# 780-00012-P1_Sch_M2_Focus_Drive_old2.net
KiCad netlist of a schematic drawn in Altium Designer
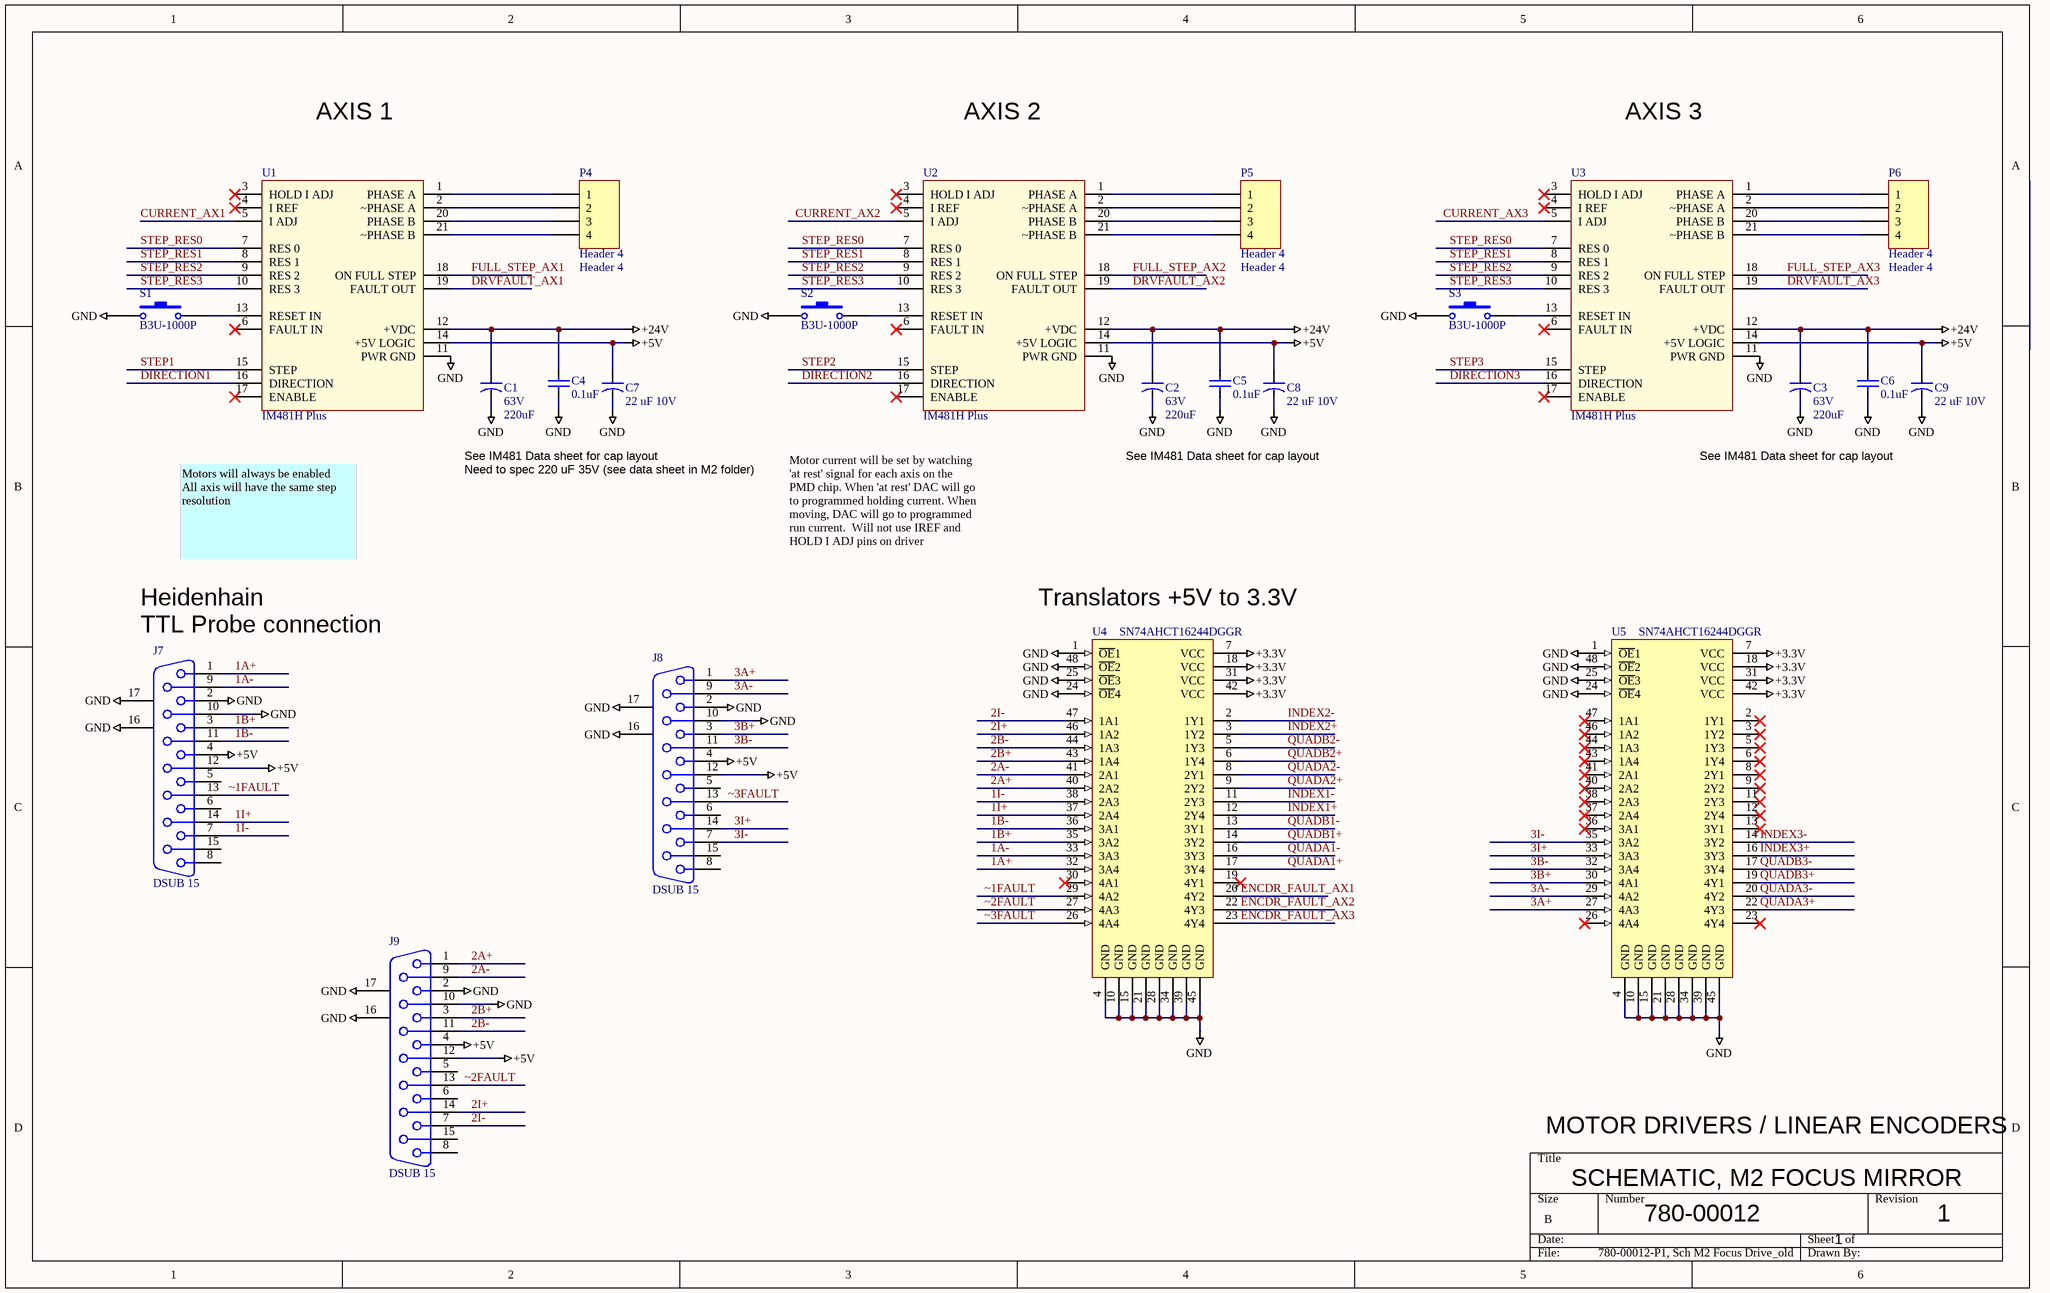
[diagram p0: 780-00012-P1, Sch M2 Focus Drive_old2.SchDoc]

(export (version "E")
  (design (tool "Eeschema 10.0.6"))
  (components
    (comp (ref "C1")
      (value "63V")
      (footprint "CAP 220uF 63V")
      (description "CAP 220UF 63V ELECT MVH SMD")
      (fields (field (name "MANUFACTURER") "United Chemi-Con") (field (name "ALTIUM_VALUE") "220uF"))
      (libsource (lib "Richs Schematic Components") (part "Cap 220uF, 63V"))
    )
    (comp (ref "C2")
      (value "63V")
      (footprint "CAP 220uF 63V")
      (description "CAP 220UF 63V ELECT MVH SMD")
      (fields (field (name "MANUFACTURER") "United Chemi-Con") (field (name "ALTIUM_VALUE") "220uF"))
      (libsource (lib "Richs Schematic Components") (part "Cap 220uF, 63V"))
    )
    (comp (ref "C3")
      (value "63V")
      (footprint "CAP 220uF 63V")
      (description "CAP 220UF 63V ELECT MVH SMD")
      (fields (field (name "MANUFACTURER") "United Chemi-Con") (field (name "ALTIUM_VALUE") "220uF"))
      (libsource (lib "Richs Schematic Components") (part "Cap 220uF, 63V"))
    )
    (comp (ref "C4")
      (value "0.1uF")
      (footprint "SMD_0805")
      (description "Capacitor")
      (fields (field (name "Comment") "Cap SMD"))
      (libsource (lib "Richs Schematic Components") (part "Cap SMD"))
    )
    (comp (ref "C5")
      (value "0.1uF")
      (footprint "SMD_0805")
      (description "Capacitor")
      (fields (field (name "Comment") "Cap SMD"))
      (libsource (lib "Richs Schematic Components") (part "Cap SMD"))
    )
    (comp (ref "C6")
      (value "0.1uF")
      (footprint "SMD_0805")
      (description "Capacitor")
      (fields (field (name "Comment") "Cap SMD"))
      (libsource (lib "Richs Schematic Components") (part "Cap SMD"))
    )
    (comp (ref "C7")
      (value "22 uF 10V")
      (footprint "SMD_CAP_3216")
      (description "outline 3.2mm x 1.6mm")
      (fields (field (name "MANUFACTURER") "KEMET") (field (name "Comment") "16V"))
      (libsource (lib "Richs Schematic Components") (part "Cap Tant 16V"))
    )
    (comp (ref "C8")
      (value "22 uF 10V")
      (footprint "SMD_CAP_3216")
      (description "outline 3.2mm x 1.6mm")
      (fields (field (name "MANUFACTURER") "KEMET") (field (name "Comment") "16V"))
      (libsource (lib "Richs Schematic Components") (part "Cap Tant 16V"))
    )
    (comp (ref "C9")
      (value "22 uF 10V")
      (footprint "SMD_CAP_3216")
      (description "outline 3.2mm x 1.6mm")
      (fields (field (name "MANUFACTURER") "KEMET") (field (name "Comment") "16V"))
      (libsource (lib "Richs Schematic Components") (part "Cap Tant 16V"))
    )
    (comp (ref "J7")
      (value "DSUB 15")
      (footprint "DSUB15 PCB VERT Female")
      (description "Receptacle Assembly, 15 Position")
      (fields (field (name "PUBLISHER") "Altium Limited"))
      (libsource (lib "Richs Schematic Components") (part "DSUB 15"))
    )
    (comp (ref "J8")
      (value "DSUB 15")
      (footprint "DSUB15 PCB VERT Female")
      (description "Receptacle Assembly, 15 Position")
      (fields (field (name "PUBLISHER") "Altium Limited"))
      (libsource (lib "Richs Schematic Components") (part "DSUB 15"))
    )
    (comp (ref "J9")
      (value "DSUB 15")
      (footprint "DSUB15 PCB VERT Female")
      (description "Receptacle Assembly, 15 Position")
      (fields (field (name "PUBLISHER") "Altium Limited"))
      (libsource (lib "Richs Schematic Components") (part "DSUB 15"))
    )
    (comp (ref "P4")
      (value "Header 4")
      (footprint "HDR1X4 for IDC")
      (description "Header, 4-Pin")
      (fields (field (name "ALTIUM_VALUE") "Header 4"))
      (libsource (lib "Richs Schematic Components") (part "Header 4"))
    )
    (comp (ref "P5")
      (value "Header 4")
      (footprint "HDR1X4 for IDC")
      (description "Header, 4-Pin")
      (fields (field (name "ALTIUM_VALUE") "Header 4"))
      (libsource (lib "Richs Schematic Components") (part "Header 4"))
    )
    (comp (ref "P6")
      (value "Header 4")
      (footprint "HDR1X4 for IDC")
      (description "Header, 4-Pin")
      (fields (field (name "ALTIUM_VALUE") "Header 4"))
      (libsource (lib "Richs Schematic Components") (part "Header 4"))
    )
    (comp (ref "S1")
      (value "B3U-1000P")
      (footprint "B3U-1000P")
      (description "Switch")
      (fields (field (name "MANUFACTURER") "Omron Electronics"))
      (libsource (lib "Miscellaneous Devices") (part "SW-PB"))
    )
    (comp (ref "S2")
      (value "B3U-1000P")
      (footprint "B3U-1000P")
      (description "Switch")
      (fields (field (name "MANUFACTURER") "Omron Electronics"))
      (libsource (lib "Miscellaneous Devices") (part "SW-PB"))
    )
    (comp (ref "S3")
      (value "B3U-1000P")
      (footprint "B3U-1000P")
      (description "Switch")
      (fields (field (name "MANUFACTURER") "Omron Electronics"))
      (libsource (lib "Miscellaneous Devices") (part "SW-PB"))
    )
    (comp (ref "U1")
      (value "IM481H Plus")
      (footprint "IM481H Vertical")
      (description "Hybrid stepper motor driver")
      (libsource (lib "Richs Schematic Components") (part "IM481H Plus"))
    )
    (comp (ref "U2")
      (value "IM481H Plus")
      (footprint "IM481H Vertical")
      (description "Hybrid stepper motor driver")
      (libsource (lib "Richs Schematic Components") (part "IM481H Plus"))
    )
    (comp (ref "U3")
      (value "IM481H Plus")
      (footprint "IM481H Vertical")
      (description "Hybrid stepper motor driver")
      (libsource (lib "Richs Schematic Components") (part "IM481H Plus"))
    )
    (comp (ref "U4")
      (value "SN74AHCT16244DGGR")
      (footprint "DGG048_N")
      (description "16-Bit Buffer/Driver with 3-State Outputs")
      (fields (field (name "PUBLISHER") "Altium Limited"))
      (libsource (lib "TI Logic Buffer Line Driver") (part "SN74AHCT16244DGGR"))
    )
    (comp (ref "U5")
      (value "SN74AHCT16244DGGR")
      (footprint "DGG048_N")
      (description "16-Bit Buffer/Driver with 3-State Outputs")
      (fields (field (name "PUBLISHER") "Altium Limited"))
      (libsource (lib "TI Logic Buffer Line Driver") (part "SN74AHCT16244DGGR"))
    )
  )
  (nets
    (net (code "1") (name "+3.3V") (class "Default")
      (node (ref "U4") (pin "18") (pinfunction "VCC_18") (pintype "power_in"))
      (node (ref "U4") (pin "31") (pinfunction "VCC_31") (pintype "power_in"))
      (node (ref "U4") (pin "42") (pinfunction "VCC_42") (pintype "power_in"))
      (node (ref "U4") (pin "7") (pinfunction "VCC_7") (pintype "power_in"))
      (node (ref "U5") (pin "18") (pinfunction "VCC_18") (pintype "power_in"))
      (node (ref "U5") (pin "31") (pinfunction "VCC_31") (pintype "power_in"))
      (node (ref "U5") (pin "42") (pinfunction "VCC_42") (pintype "power_in"))
      (node (ref "U5") (pin "7") (pinfunction "VCC_7") (pintype "power_in"))
    )
    (net (code "2") (name "+5V") (class "Default")
      (node (ref "C7") (pin "1") (pinfunction "1_1") (pintype "passive"))
      (node (ref "C8") (pin "1") (pinfunction "1_1") (pintype "passive"))
      (node (ref "C9") (pin "1") (pinfunction "1_1") (pintype "passive"))
      (node (ref "J7") (pin "12") (pinfunction "12_12") (pintype "passive"))
      (node (ref "J7") (pin "4") (pinfunction "4_4") (pintype "passive"))
      (node (ref "J8") (pin "12") (pinfunction "12_12") (pintype "passive"))
      (node (ref "J8") (pin "4") (pinfunction "4_4") (pintype "passive"))
      (node (ref "J9") (pin "12") (pinfunction "12_12") (pintype "passive"))
      (node (ref "J9") (pin "4") (pinfunction "4_4") (pintype "passive"))
      (node (ref "U1") (pin "14") (pinfunction "+5V_LOGIC_14") (pintype "passive"))
      (node (ref "U2") (pin "14") (pinfunction "+5V_LOGIC_14") (pintype "passive"))
      (node (ref "U3") (pin "14") (pinfunction "+5V_LOGIC_14") (pintype "passive"))
    )
    (net (code "3") (name "+24V") (class "Default")
      (node (ref "C1") (pin "1") (pinfunction "1_1") (pintype "passive"))
      (node (ref "C2") (pin "1") (pinfunction "1_1") (pintype "passive"))
      (node (ref "C3") (pin "1") (pinfunction "1_1") (pintype "passive"))
      (node (ref "C4") (pin "2") (pinfunction "2_2") (pintype "passive"))
      (node (ref "C5") (pin "2") (pinfunction "2_2") (pintype "passive"))
      (node (ref "C6") (pin "2") (pinfunction "2_2") (pintype "passive"))
      (node (ref "U1") (pin "12") (pinfunction "+VDC_12") (pintype "passive"))
      (node (ref "U2") (pin "12") (pinfunction "+VDC_12") (pintype "passive"))
      (node (ref "U3") (pin "12") (pinfunction "+VDC_12") (pintype "passive"))
    )
    (net (code "4") (name "/1A+") (class "Default")
      (node (ref "J7") (pin "1") (pinfunction "1_1") (pintype "passive"))
      (node (ref "U4") (pin "32") (pinfunction "3A4_32") (pintype "input"))
    )
    (net (code "5") (name "/1A-") (class "Default")
      (node (ref "J7") (pin "9") (pinfunction "9_9") (pintype "passive"))
      (node (ref "U4") (pin "33") (pinfunction "3A3_33") (pintype "input"))
    )
    (net (code "6") (name "/1B+") (class "Default")
      (node (ref "J7") (pin "3") (pinfunction "3_3") (pintype "passive"))
      (node (ref "U4") (pin "35") (pinfunction "3A2_35") (pintype "input"))
    )
    (net (code "7") (name "/1B-") (class "Default")
      (node (ref "J7") (pin "11") (pinfunction "11_11") (pintype "passive"))
      (node (ref "U4") (pin "36") (pinfunction "3A1_36") (pintype "input"))
    )
    (net (code "8") (name "/1I+") (class "Default")
      (node (ref "J7") (pin "14") (pinfunction "14_14") (pintype "passive"))
      (node (ref "U4") (pin "37") (pinfunction "2A4_37") (pintype "input"))
    )
    (net (code "9") (name "/1I-") (class "Default")
      (node (ref "J7") (pin "7") (pinfunction "7_7") (pintype "passive"))
      (node (ref "U4") (pin "38") (pinfunction "2A3_38") (pintype "input"))
    )
    (net (code "10") (name "/2A+") (class "Default")
      (node (ref "J9") (pin "1") (pinfunction "1_1") (pintype "passive"))
      (node (ref "U4") (pin "40") (pinfunction "2A2_40") (pintype "input"))
    )
    (net (code "11") (name "/2A-") (class "Default")
      (node (ref "J9") (pin "9") (pinfunction "9_9") (pintype "passive"))
      (node (ref "U4") (pin "41") (pinfunction "2A1_41") (pintype "input"))
    )
    (net (code "12") (name "/2B+") (class "Default")
      (node (ref "J9") (pin "3") (pinfunction "3_3") (pintype "passive"))
      (node (ref "U4") (pin "43") (pinfunction "1A4_43") (pintype "input"))
    )
    (net (code "13") (name "/2B-") (class "Default")
      (node (ref "J9") (pin "11") (pinfunction "11_11") (pintype "passive"))
      (node (ref "U4") (pin "44") (pinfunction "1A3_44") (pintype "input"))
    )
    (net (code "14") (name "/2I+") (class "Default")
      (node (ref "J9") (pin "14") (pinfunction "14_14") (pintype "passive"))
      (node (ref "U4") (pin "46") (pinfunction "1A2_46") (pintype "input"))
    )
    (net (code "15") (name "/2I-") (class "Default")
      (node (ref "J9") (pin "7") (pinfunction "7_7") (pintype "passive"))
      (node (ref "U4") (pin "47") (pinfunction "1A1_47") (pintype "input"))
    )
    (net (code "16") (name "/3A+") (class "Default")
      (node (ref "J8") (pin "1") (pinfunction "1_1") (pintype "passive"))
      (node (ref "U5") (pin "27") (pinfunction "4A3_27") (pintype "input"))
    )
    (net (code "17") (name "/3A-") (class "Default")
      (node (ref "J8") (pin "9") (pinfunction "9_9") (pintype "passive"))
      (node (ref "U5") (pin "29") (pinfunction "4A2_29") (pintype "input"))
    )
    (net (code "18") (name "/3B+") (class "Default")
      (node (ref "J8") (pin "3") (pinfunction "3_3") (pintype "passive"))
      (node (ref "U5") (pin "30") (pinfunction "4A1_30") (pintype "input"))
    )
    (net (code "19") (name "/3B-") (class "Default")
      (node (ref "J8") (pin "11") (pinfunction "11_11") (pintype "passive"))
      (node (ref "U5") (pin "32") (pinfunction "3A4_32") (pintype "input"))
    )
    (net (code "20") (name "/3I+") (class "Default")
      (node (ref "J8") (pin "14") (pinfunction "14_14") (pintype "passive"))
      (node (ref "U5") (pin "33") (pinfunction "3A3_33") (pintype "input"))
    )
    (net (code "21") (name "/3I-") (class "Default")
      (node (ref "J8") (pin "7") (pinfunction "7_7") (pintype "passive"))
      (node (ref "U5") (pin "35") (pinfunction "3A2_35") (pintype "input"))
    )
    (net (code "22") (name "/CURRENT_AX1") (class "Default")
      (node (ref "U1") (pin "5") (pinfunction "I_ADJ_5") (pintype "passive"))
    )
    (net (code "23") (name "/CURRENT_AX2") (class "Default")
      (node (ref "U2") (pin "5") (pinfunction "I_ADJ_5") (pintype "passive"))
    )
    (net (code "24") (name "/CURRENT_AX3") (class "Default")
      (node (ref "U3") (pin "5") (pinfunction "I_ADJ_5") (pintype "passive"))
    )
    (net (code "25") (name "/DIRECTION1") (class "Default")
      (node (ref "U1") (pin "16") (pinfunction "DIRECTION_16") (pintype "passive"))
    )
    (net (code "26") (name "/DIRECTION2") (class "Default")
      (node (ref "U2") (pin "16") (pinfunction "DIRECTION_16") (pintype "passive"))
    )
    (net (code "27") (name "/DIRECTION3") (class "Default")
      (node (ref "U3") (pin "16") (pinfunction "DIRECTION_16") (pintype "passive"))
    )
    (net (code "28") (name "/DRVFAULT_AX1") (class "Default")
      (node (ref "U1") (pin "19") (pinfunction "FAULT_OUT_19") (pintype "passive"))
    )
    (net (code "29") (name "/DRVFAULT_AX2") (class "Default")
      (node (ref "U2") (pin "19") (pinfunction "FAULT_OUT_19") (pintype "passive"))
    )
    (net (code "30") (name "/DRVFAULT_AX3") (class "Default")
      (node (ref "U3") (pin "19") (pinfunction "FAULT_OUT_19") (pintype "passive"))
    )
    (net (code "31") (name "/ENCDR_FAULT_AX1") (class "Default")
      (node (ref "U4") (pin "20") (pinfunction "4Y2_20") (pintype "tri_state"))
    )
    (net (code "32") (name "/ENCDR_FAULT_AX2") (class "Default")
      (node (ref "U4") (pin "22") (pinfunction "4Y3_22") (pintype "tri_state"))
    )
    (net (code "33") (name "/ENCDR_FAULT_AX3") (class "Default")
      (node (ref "U4") (pin "23") (pinfunction "4Y4_23") (pintype "tri_state"))
    )
    (net (code "34") (name "/FULL_STEP_AX1") (class "Default")
      (node (ref "U1") (pin "18") (pinfunction "ON_FULL_STEP_18") (pintype "passive"))
    )
    (net (code "35") (name "/FULL_STEP_AX2") (class "Default")
      (node (ref "U2") (pin "18") (pinfunction "ON_FULL_STEP_18") (pintype "passive"))
    )
    (net (code "36") (name "/FULL_STEP_AX3") (class "Default")
      (node (ref "U3") (pin "18") (pinfunction "ON_FULL_STEP_18") (pintype "passive"))
    )
    (net (code "37") (name "/INDEX1+") (class "Default")
      (node (ref "U4") (pin "12") (pinfunction "2Y4_12") (pintype "tri_state"))
    )
    (net (code "38") (name "/INDEX1-") (class "Default")
      (node (ref "U4") (pin "11") (pinfunction "2Y3_11") (pintype "tri_state"))
    )
    (net (code "39") (name "/INDEX2+") (class "Default")
      (node (ref "U4") (pin "3") (pinfunction "1Y2_3") (pintype "tri_state"))
    )
    (net (code "40") (name "/INDEX2-") (class "Default")
      (node (ref "U4") (pin "2") (pinfunction "1Y1_2") (pintype "tri_state"))
    )
    (net (code "41") (name "/INDEX3+") (class "Default")
      (node (ref "U5") (pin "16") (pinfunction "3Y3_16") (pintype "tri_state"))
    )
    (net (code "42") (name "/INDEX3-") (class "Default")
      (node (ref "U5") (pin "14") (pinfunction "3Y2_14") (pintype "tri_state"))
    )
    (net (code "43") (name "/QUADA1+") (class "Default")
      (node (ref "U4") (pin "17") (pinfunction "3Y4_17") (pintype "tri_state"))
    )
    (net (code "44") (name "/QUADA1-") (class "Default")
      (node (ref "U4") (pin "16") (pinfunction "3Y3_16") (pintype "tri_state"))
    )
    (net (code "45") (name "/QUADA2+") (class "Default")
      (node (ref "U4") (pin "9") (pinfunction "2Y2_9") (pintype "tri_state"))
    )
    (net (code "46") (name "/QUADA2-") (class "Default")
      (node (ref "U4") (pin "8") (pinfunction "2Y1_8") (pintype "tri_state"))
    )
    (net (code "47") (name "/QUADA3+") (class "Default")
      (node (ref "U5") (pin "22") (pinfunction "4Y3_22") (pintype "tri_state"))
    )
    (net (code "48") (name "/QUADA3-") (class "Default")
      (node (ref "U5") (pin "20") (pinfunction "4Y2_20") (pintype "tri_state"))
    )
    (net (code "49") (name "/QUADB1+") (class "Default")
      (node (ref "U4") (pin "14") (pinfunction "3Y2_14") (pintype "tri_state"))
    )
    (net (code "50") (name "/QUADB1-") (class "Default")
      (node (ref "U4") (pin "13") (pinfunction "3Y1_13") (pintype "tri_state"))
    )
    (net (code "51") (name "/QUADB2+") (class "Default")
      (node (ref "U4") (pin "6") (pinfunction "1Y4_6") (pintype "tri_state"))
    )
    (net (code "52") (name "/QUADB2-") (class "Default")
      (node (ref "U4") (pin "5") (pinfunction "1Y3_5") (pintype "tri_state"))
    )
    (net (code "53") (name "/QUADB3+") (class "Default")
      (node (ref "U5") (pin "19") (pinfunction "4Y1_19") (pintype "tri_state"))
    )
    (net (code "54") (name "/QUADB3-") (class "Default")
      (node (ref "U5") (pin "17") (pinfunction "3Y4_17") (pintype "tri_state"))
    )
    (net (code "55") (name "/STEP1") (class "Default")
      (node (ref "U1") (pin "15") (pinfunction "STEP_15") (pintype "passive"))
    )
    (net (code "56") (name "/STEP2") (class "Default")
      (node (ref "U2") (pin "15") (pinfunction "STEP_15") (pintype "passive"))
    )
    (net (code "57") (name "/STEP3") (class "Default")
      (node (ref "U3") (pin "15") (pinfunction "STEP_15") (pintype "passive"))
    )
    (net (code "58") (name "/STEP_RES0") (class "Default")
      (node (ref "U1") (pin "7") (pinfunction "RES_0_7") (pintype "passive"))
      (node (ref "U2") (pin "7") (pinfunction "RES_0_7") (pintype "passive"))
      (node (ref "U3") (pin "7") (pinfunction "RES_0_7") (pintype "passive"))
    )
    (net (code "59") (name "/STEP_RES1") (class "Default")
      (node (ref "U1") (pin "8") (pinfunction "RES_1_8") (pintype "passive"))
      (node (ref "U2") (pin "8") (pinfunction "RES_1_8") (pintype "passive"))
      (node (ref "U3") (pin "8") (pinfunction "RES_1_8") (pintype "passive"))
    )
    (net (code "60") (name "/STEP_RES2") (class "Default")
      (node (ref "U1") (pin "9") (pinfunction "RES_2_9") (pintype "passive"))
      (node (ref "U2") (pin "9") (pinfunction "RES_2_9") (pintype "passive"))
      (node (ref "U3") (pin "9") (pinfunction "RES_2_9") (pintype "passive"))
    )
    (net (code "61") (name "/STEP_RES3") (class "Default")
      (node (ref "U1") (pin "10") (pinfunction "RES_3_10") (pintype "passive"))
      (node (ref "U2") (pin "10") (pinfunction "RES_3_10") (pintype "passive"))
      (node (ref "U3") (pin "10") (pinfunction "RES_3_10") (pintype "passive"))
    )
    (net (code "62") (name "/~1FAULT") (class "Default")
      (node (ref "J7") (pin "13") (pinfunction "13_13") (pintype "passive"))
      (node (ref "U4") (pin "29") (pinfunction "4A2_29") (pintype "input"))
    )
    (net (code "63") (name "/~2FAULT") (class "Default")
      (node (ref "J9") (pin "13") (pinfunction "13_13") (pintype "passive"))
      (node (ref "U4") (pin "27") (pinfunction "4A3_27") (pintype "input"))
    )
    (net (code "64") (name "/~3FAULT") (class "Default")
      (node (ref "J8") (pin "13") (pinfunction "13_13") (pintype "passive"))
      (node (ref "U4") (pin "26") (pinfunction "4A4_26") (pintype "input"))
    )
    (net (code "65") (name "GND") (class "Default")
      (node (ref "C1") (pin "2") (pinfunction "2_2") (pintype "passive"))
      (node (ref "C2") (pin "2") (pinfunction "2_2") (pintype "passive"))
      (node (ref "C3") (pin "2") (pinfunction "2_2") (pintype "passive"))
      (node (ref "C4") (pin "1") (pinfunction "1_1") (pintype "passive"))
      (node (ref "C5") (pin "1") (pinfunction "1_1") (pintype "passive"))
      (node (ref "C6") (pin "1") (pinfunction "1_1") (pintype "passive"))
      (node (ref "C7") (pin "2") (pinfunction "2_2") (pintype "passive"))
      (node (ref "C8") (pin "2") (pinfunction "2_2") (pintype "passive"))
      (node (ref "C9") (pin "2") (pinfunction "2_2") (pintype "passive"))
      (node (ref "J7") (pin "10") (pinfunction "10_10") (pintype "passive"))
      (node (ref "J7") (pin "16") (pinfunction "MH1_16") (pintype "passive"))
      (node (ref "J7") (pin "17") (pinfunction "MH2_17") (pintype "passive"))
      (node (ref "J7") (pin "2") (pinfunction "2_2") (pintype "passive"))
      (node (ref "J8") (pin "10") (pinfunction "10_10") (pintype "passive"))
      (node (ref "J8") (pin "16") (pinfunction "MH1_16") (pintype "passive"))
      (node (ref "J8") (pin "17") (pinfunction "MH2_17") (pintype "passive"))
      (node (ref "J8") (pin "2") (pinfunction "2_2") (pintype "passive"))
      (node (ref "J9") (pin "10") (pinfunction "10_10") (pintype "passive"))
      (node (ref "J9") (pin "16") (pinfunction "MH1_16") (pintype "passive"))
      (node (ref "J9") (pin "17") (pinfunction "MH2_17") (pintype "passive"))
      (node (ref "J9") (pin "2") (pinfunction "2_2") (pintype "passive"))
      (node (ref "S1") (pin "1") (pinfunction "1_1") (pintype "passive"))
      (node (ref "S2") (pin "1") (pinfunction "1_1") (pintype "passive"))
      (node (ref "S3") (pin "1") (pinfunction "1_1") (pintype "passive"))
      (node (ref "U1") (pin "11") (pinfunction "PWR_GND_11") (pintype "passive"))
      (node (ref "U2") (pin "11") (pinfunction "PWR_GND_11") (pintype "passive"))
      (node (ref "U3") (pin "11") (pinfunction "PWR_GND_11") (pintype "passive"))
      (node (ref "U4") (pin "1") (pinfunction "~{OE}1_1") (pintype "input"))
      (node (ref "U4") (pin "10") (pinfunction "GND_10") (pintype "power_in"))
      (node (ref "U4") (pin "15") (pinfunction "GND_15") (pintype "power_in"))
      (node (ref "U4") (pin "21") (pinfunction "GND_21") (pintype "power_in"))
      (node (ref "U4") (pin "24") (pinfunction "~{OE}4_24") (pintype "input"))
      (node (ref "U4") (pin "25") (pinfunction "~{OE}3_25") (pintype "input"))
      (node (ref "U4") (pin "28") (pinfunction "GND_28") (pintype "power_in"))
      (node (ref "U4") (pin "34") (pinfunction "GND_34") (pintype "power_in"))
      (node (ref "U4") (pin "39") (pinfunction "GND_39") (pintype "power_in"))
      (node (ref "U4") (pin "4") (pinfunction "GND_4") (pintype "power_in"))
      (node (ref "U4") (pin "45") (pinfunction "GND_45") (pintype "power_in"))
      (node (ref "U4") (pin "48") (pinfunction "~{OE}2_48") (pintype "input"))
      (node (ref "U5") (pin "1") (pinfunction "~{OE}1_1") (pintype "input"))
      (node (ref "U5") (pin "10") (pinfunction "GND_10") (pintype "power_in"))
      (node (ref "U5") (pin "15") (pinfunction "GND_15") (pintype "power_in"))
      (node (ref "U5") (pin "21") (pinfunction "GND_21") (pintype "power_in"))
      (node (ref "U5") (pin "24") (pinfunction "~{OE}4_24") (pintype "input"))
      (node (ref "U5") (pin "25") (pinfunction "~{OE}3_25") (pintype "input"))
      (node (ref "U5") (pin "28") (pinfunction "GND_28") (pintype "power_in"))
      (node (ref "U5") (pin "34") (pinfunction "GND_34") (pintype "power_in"))
      (node (ref "U5") (pin "39") (pinfunction "GND_39") (pintype "power_in"))
      (node (ref "U5") (pin "4") (pinfunction "GND_4") (pintype "power_in"))
      (node (ref "U5") (pin "45") (pinfunction "GND_45") (pintype "power_in"))
      (node (ref "U5") (pin "48") (pinfunction "~{OE}2_48") (pintype "input"))
    )
    (net (code "66") (name "Net-(U1-PHASE_A)") (class "Default")
      (node (ref "P4") (pin "1") (pinfunction "1_1") (pintype "passive"))
      (node (ref "U1") (pin "1") (pinfunction "PHASE_A_1") (pintype "passive"))
    )
    (net (code "67") (name "Net-(U1-PHASE_B)") (class "Default")
      (node (ref "P4") (pin "3") (pinfunction "3_3") (pintype "passive"))
      (node (ref "U1") (pin "20") (pinfunction "PHASE_B_20") (pintype "passive"))
    )
    (net (code "68") (name "Net-(U1-RESET_IN)") (class "Default")
      (node (ref "S1") (pin "2") (pinfunction "2_2") (pintype "passive"))
      (node (ref "U1") (pin "13") (pinfunction "RESET_IN_13") (pintype "passive"))
    )
    (net (code "69") (name "Net-(U1-~PHASE_A)") (class "Default")
      (node (ref "P4") (pin "2") (pinfunction "2_2") (pintype "passive"))
      (node (ref "U1") (pin "2") (pinfunction "~PHASE_A_2") (pintype "passive"))
    )
    (net (code "70") (name "Net-(U1-~PHASE_B)") (class "Default")
      (node (ref "P4") (pin "4") (pinfunction "4_4") (pintype "passive"))
      (node (ref "U1") (pin "21") (pinfunction "~PHASE_B_21") (pintype "passive"))
    )
    (net (code "71") (name "Net-(U2-PHASE_A)") (class "Default")
      (node (ref "P5") (pin "1") (pinfunction "1_1") (pintype "passive"))
      (node (ref "U2") (pin "1") (pinfunction "PHASE_A_1") (pintype "passive"))
    )
    (net (code "72") (name "Net-(U2-PHASE_B)") (class "Default")
      (node (ref "P5") (pin "3") (pinfunction "3_3") (pintype "passive"))
      (node (ref "U2") (pin "20") (pinfunction "PHASE_B_20") (pintype "passive"))
    )
    (net (code "73") (name "Net-(U2-RESET_IN)") (class "Default")
      (node (ref "S2") (pin "2") (pinfunction "2_2") (pintype "passive"))
      (node (ref "U2") (pin "13") (pinfunction "RESET_IN_13") (pintype "passive"))
    )
    (net (code "74") (name "Net-(U2-~PHASE_A)") (class "Default")
      (node (ref "P5") (pin "2") (pinfunction "2_2") (pintype "passive"))
      (node (ref "U2") (pin "2") (pinfunction "~PHASE_A_2") (pintype "passive"))
    )
    (net (code "75") (name "Net-(U2-~PHASE_B)") (class "Default")
      (node (ref "P5") (pin "4") (pinfunction "4_4") (pintype "passive"))
      (node (ref "U2") (pin "21") (pinfunction "~PHASE_B_21") (pintype "passive"))
    )
    (net (code "76") (name "Net-(U3-PHASE_A)") (class "Default")
      (node (ref "P6") (pin "1") (pinfunction "1_1") (pintype "passive"))
      (node (ref "U3") (pin "1") (pinfunction "PHASE_A_1") (pintype "passive"))
    )
    (net (code "77") (name "Net-(U3-PHASE_B)") (class "Default")
      (node (ref "P6") (pin "3") (pinfunction "3_3") (pintype "passive"))
      (node (ref "U3") (pin "20") (pinfunction "PHASE_B_20") (pintype "passive"))
    )
    (net (code "78") (name "Net-(U3-RESET_IN)") (class "Default")
      (node (ref "S3") (pin "2") (pinfunction "2_2") (pintype "passive"))
      (node (ref "U3") (pin "13") (pinfunction "RESET_IN_13") (pintype "passive"))
    )
    (net (code "79") (name "Net-(U3-~PHASE_A)") (class "Default")
      (node (ref "P6") (pin "2") (pinfunction "2_2") (pintype "passive"))
      (node (ref "U3") (pin "2") (pinfunction "~PHASE_A_2") (pintype "passive"))
    )
    (net (code "80") (name "Net-(U3-~PHASE_B)") (class "Default")
      (node (ref "P6") (pin "4") (pinfunction "4_4") (pintype "passive"))
      (node (ref "U3") (pin "21") (pinfunction "~PHASE_B_21") (pintype "passive"))
    )
    (net (code "81") (name "unconnected-(J7-Pad5)") (class "Default")
      (node (ref "J7") (pin "5") (pinfunction "5_5") (pintype "passive"))
    )
    (net (code "82") (name "unconnected-(J7-Pad6)") (class "Default")
      (node (ref "J7") (pin "6") (pinfunction "6_6") (pintype "passive"))
    )
    (net (code "83") (name "unconnected-(J7-Pad8)") (class "Default")
      (node (ref "J7") (pin "8") (pinfunction "8_8") (pintype "passive"))
    )
    (net (code "84") (name "unconnected-(J7-Pad15)") (class "Default")
      (node (ref "J7") (pin "15") (pinfunction "15_15") (pintype "passive"))
    )
    (net (code "85") (name "unconnected-(J8-Pad5)") (class "Default")
      (node (ref "J8") (pin "5") (pinfunction "5_5") (pintype "passive"))
    )
    (net (code "86") (name "unconnected-(J8-Pad6)") (class "Default")
      (node (ref "J8") (pin "6") (pinfunction "6_6") (pintype "passive"))
    )
    (net (code "87") (name "unconnected-(J8-Pad8)") (class "Default")
      (node (ref "J8") (pin "8") (pinfunction "8_8") (pintype "passive"))
    )
    (net (code "88") (name "unconnected-(J8-Pad15)") (class "Default")
      (node (ref "J8") (pin "15") (pinfunction "15_15") (pintype "passive"))
    )
    (net (code "89") (name "unconnected-(J9-Pad5)") (class "Default")
      (node (ref "J9") (pin "5") (pinfunction "5_5") (pintype "passive"))
    )
    (net (code "90") (name "unconnected-(J9-Pad6)") (class "Default")
      (node (ref "J9") (pin "6") (pinfunction "6_6") (pintype "passive"))
    )
    (net (code "91") (name "unconnected-(J9-Pad8)") (class "Default")
      (node (ref "J9") (pin "8") (pinfunction "8_8") (pintype "passive"))
    )
    (net (code "92") (name "unconnected-(J9-Pad15)") (class "Default")
      (node (ref "J9") (pin "15") (pinfunction "15_15") (pintype "passive"))
    )
    (net (code "93") (name "unconnected-(U1-ENABLE-Pad17)") (class "Default")
      (node (ref "U1") (pin "17") (pinfunction "ENABLE_17") (pintype "passive+no_connect"))
    )
    (net (code "94") (name "unconnected-(U1-FAULT_IN-Pad6)") (class "Default")
      (node (ref "U1") (pin "6") (pinfunction "FAULT_IN_6") (pintype "passive+no_connect"))
    )
    (net (code "95") (name "unconnected-(U1-HOLD_I_ADJ-Pad3)") (class "Default")
      (node (ref "U1") (pin "3") (pinfunction "HOLD_I_ADJ_3") (pintype "passive+no_connect"))
    )
    (net (code "96") (name "unconnected-(U1-I_REF-Pad4)") (class "Default")
      (node (ref "U1") (pin "4") (pinfunction "I_REF_4") (pintype "passive+no_connect"))
    )
    (net (code "97") (name "unconnected-(U2-ENABLE-Pad17)") (class "Default")
      (node (ref "U2") (pin "17") (pinfunction "ENABLE_17") (pintype "passive+no_connect"))
    )
    (net (code "98") (name "unconnected-(U2-FAULT_IN-Pad6)") (class "Default")
      (node (ref "U2") (pin "6") (pinfunction "FAULT_IN_6") (pintype "passive+no_connect"))
    )
    (net (code "99") (name "unconnected-(U2-HOLD_I_ADJ-Pad3)") (class "Default")
      (node (ref "U2") (pin "3") (pinfunction "HOLD_I_ADJ_3") (pintype "passive+no_connect"))
    )
    (net (code "100") (name "unconnected-(U2-I_REF-Pad4)") (class "Default")
      (node (ref "U2") (pin "4") (pinfunction "I_REF_4") (pintype "passive+no_connect"))
    )
    (net (code "101") (name "unconnected-(U3-ENABLE-Pad17)") (class "Default")
      (node (ref "U3") (pin "17") (pinfunction "ENABLE_17") (pintype "passive+no_connect"))
    )
    (net (code "102") (name "unconnected-(U3-FAULT_IN-Pad6)") (class "Default")
      (node (ref "U3") (pin "6") (pinfunction "FAULT_IN_6") (pintype "passive+no_connect"))
    )
    (net (code "103") (name "unconnected-(U3-HOLD_I_ADJ-Pad3)") (class "Default")
      (node (ref "U3") (pin "3") (pinfunction "HOLD_I_ADJ_3") (pintype "passive+no_connect"))
    )
    (net (code "104") (name "unconnected-(U3-I_REF-Pad4)") (class "Default")
      (node (ref "U3") (pin "4") (pinfunction "I_REF_4") (pintype "passive+no_connect"))
    )
    (net (code "105") (name "unconnected-(U4-4A1-Pad30)") (class "Default")
      (node (ref "U4") (pin "30") (pinfunction "4A1_30") (pintype "input+no_connect"))
    )
    (net (code "106") (name "unconnected-(U4-4Y1-Pad19)") (class "Default")
      (node (ref "U4") (pin "19") (pinfunction "4Y1_19") (pintype "tri_state+no_connect"))
    )
    (net (code "107") (name "unconnected-(U5-1A1-Pad47)") (class "Default")
      (node (ref "U5") (pin "47") (pinfunction "1A1_47") (pintype "input+no_connect"))
    )
    (net (code "108") (name "unconnected-(U5-1A2-Pad46)") (class "Default")
      (node (ref "U5") (pin "46") (pinfunction "1A2_46") (pintype "input+no_connect"))
    )
    (net (code "109") (name "unconnected-(U5-1A3-Pad44)") (class "Default")
      (node (ref "U5") (pin "44") (pinfunction "1A3_44") (pintype "input+no_connect"))
    )
    (net (code "110") (name "unconnected-(U5-1A4-Pad43)") (class "Default")
      (node (ref "U5") (pin "43") (pinfunction "1A4_43") (pintype "input+no_connect"))
    )
    (net (code "111") (name "unconnected-(U5-1Y1-Pad2)") (class "Default")
      (node (ref "U5") (pin "2") (pinfunction "1Y1_2") (pintype "tri_state+no_connect"))
    )
    (net (code "112") (name "unconnected-(U5-1Y2-Pad3)") (class "Default")
      (node (ref "U5") (pin "3") (pinfunction "1Y2_3") (pintype "tri_state+no_connect"))
    )
    (net (code "113") (name "unconnected-(U5-1Y3-Pad5)") (class "Default")
      (node (ref "U5") (pin "5") (pinfunction "1Y3_5") (pintype "tri_state+no_connect"))
    )
    (net (code "114") (name "unconnected-(U5-1Y4-Pad6)") (class "Default")
      (node (ref "U5") (pin "6") (pinfunction "1Y4_6") (pintype "tri_state+no_connect"))
    )
    (net (code "115") (name "unconnected-(U5-2A1-Pad41)") (class "Default")
      (node (ref "U5") (pin "41") (pinfunction "2A1_41") (pintype "input+no_connect"))
    )
    (net (code "116") (name "unconnected-(U5-2A2-Pad40)") (class "Default")
      (node (ref "U5") (pin "40") (pinfunction "2A2_40") (pintype "input+no_connect"))
    )
    (net (code "117") (name "unconnected-(U5-2A3-Pad38)") (class "Default")
      (node (ref "U5") (pin "38") (pinfunction "2A3_38") (pintype "input+no_connect"))
    )
    (net (code "118") (name "unconnected-(U5-2A4-Pad37)") (class "Default")
      (node (ref "U5") (pin "37") (pinfunction "2A4_37") (pintype "input+no_connect"))
    )
    (net (code "119") (name "unconnected-(U5-2Y1-Pad8)") (class "Default")
      (node (ref "U5") (pin "8") (pinfunction "2Y1_8") (pintype "tri_state+no_connect"))
    )
    (net (code "120") (name "unconnected-(U5-2Y2-Pad9)") (class "Default")
      (node (ref "U5") (pin "9") (pinfunction "2Y2_9") (pintype "tri_state+no_connect"))
    )
    (net (code "121") (name "unconnected-(U5-2Y3-Pad11)") (class "Default")
      (node (ref "U5") (pin "11") (pinfunction "2Y3_11") (pintype "tri_state+no_connect"))
    )
    (net (code "122") (name "unconnected-(U5-2Y4-Pad12)") (class "Default")
      (node (ref "U5") (pin "12") (pinfunction "2Y4_12") (pintype "tri_state+no_connect"))
    )
    (net (code "123") (name "unconnected-(U5-3A1-Pad36)") (class "Default")
      (node (ref "U5") (pin "36") (pinfunction "3A1_36") (pintype "input+no_connect"))
    )
    (net (code "124") (name "unconnected-(U5-3Y1-Pad13)") (class "Default")
      (node (ref "U5") (pin "13") (pinfunction "3Y1_13") (pintype "tri_state+no_connect"))
    )
    (net (code "125") (name "unconnected-(U5-4A4-Pad26)") (class "Default")
      (node (ref "U5") (pin "26") (pinfunction "4A4_26") (pintype "input+no_connect"))
    )
    (net (code "126") (name "unconnected-(U5-4Y4-Pad23)") (class "Default")
      (node (ref "U5") (pin "23") (pinfunction "4Y4_23") (pintype "tri_state+no_connect"))
    )
  )
)
